# Blown_Fuse_LED.net
KiCad netlist of a schematic drawn in Altium Designer
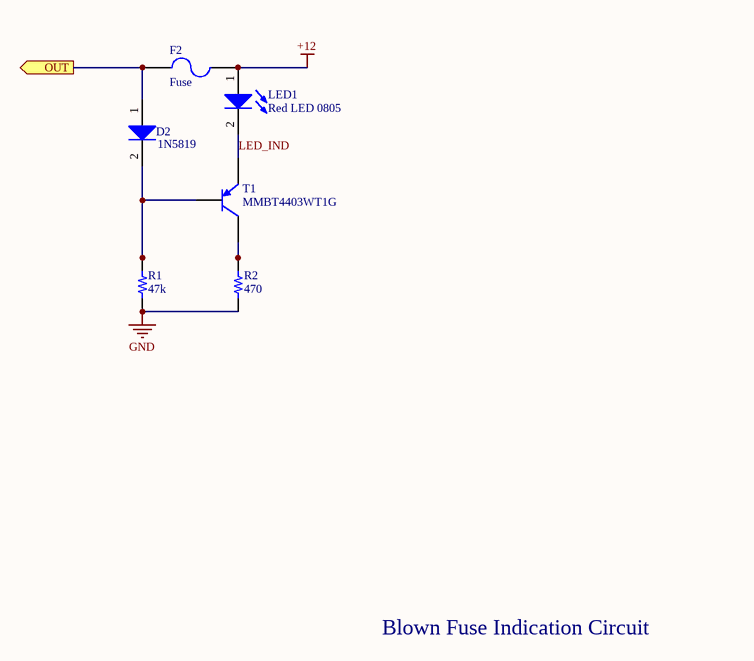
[diagram p0: Blown_Fuse_LED.SchDoc]

(export (version "E")
  (design (tool "Eeschema 10.0.6"))
  (components
    (comp (ref "D2")
      (value "1N5819")
      (footprint "SOD123F")
      (description "Diode Super Barrier 40V 1A Surface Mount SOD-123F")
      (fields (field (name "POWER") "40V") (field (name "MFRPARTNO") "1N5819HW1-7-F"))
      (libsource (lib "Altium-Lib") (part "DIODE"))
    )
    (comp (ref "F2")
      (value "Fuse")
      (footprint "3568-MiniFuseHolder")
      (libsource (lib "Altium-Lib") (part "Fuse"))
    )
    (comp (ref "LED1")
      (value "Red LED 0805")
      (footprint "0805_LED")
      (libsource (lib "Altium-Lib") (part "LED"))
    )
    (comp (ref "R1")
      (value "47k")
      (footprint "RES 0805/2012")
      (fields
        (field (name "TOLERANCE") "1%")
        (field (name "POWER") "1/10W")
        (field (name "Comment") "Resistor 47k 0805 1/10W 1%")
        (field (name "CREATED_BY") "Nick Mah")
      )
      (libsource (lib "Altium-Lib") (part "Resistor"))
    )
    (comp (ref "R2")
      (value "470")
      (footprint "RES 0805/2012")
      (fields
        (field (name "TOLERANCE") "1%")
        (field (name "POWER") "1/10W")
        (field (name "Comment") "Resistor 470 0805 1/10W 1%")
        (field (name "CREATED_BY") "Nick Mah")
      )
      (libsource (lib "Altium-Lib") (part "Resistor"))
    )
    (comp (ref "T1")
      (value "MMBT4403WT1G")
      (footprint "SOT23-3")
      (fields (field (name "CREATED_BY") "Angel"))
      (libsource (lib "Altium-Lib") (part "PNP Transistor"))
    )
  )
  (nets
    (net (code "1") (name "+12") (class "Default")
      (node (ref "F2") (pin "2") (pinfunction "2_2") (pintype "passive"))
      (node (ref "LED1") (pin "1") (pinfunction "A_1") (pintype "passive"))
    )
    (net (code "2") (name "/LED_IND") (class "Default")
      (node (ref "LED1") (pin "2") (pinfunction "K_2") (pintype "passive"))
      (node (ref "T1") (pin "2") (pinfunction "E_2") (pintype "passive"))
    )
    (net (code "3") (name "/OUT") (class "Default")
      (node (ref "D2") (pin "1") (pinfunction "A_1") (pintype "passive"))
      (node (ref "F2") (pin "1") (pinfunction "1_1") (pintype "passive"))
    )
    (net (code "4") (name "GND") (class "Default")
      (node (ref "R1") (pin "2") (pinfunction "2_2") (pintype "passive"))
      (node (ref "R2") (pin "2") (pinfunction "2_2") (pintype "passive"))
    )
    (net (code "5") (name "Net-(D2-K)") (class "Default")
      (node (ref "D2") (pin "2") (pinfunction "K_2") (pintype "passive"))
      (node (ref "R1") (pin "1") (pinfunction "1_1") (pintype "passive"))
      (node (ref "T1") (pin "1") (pinfunction "B_1") (pintype "passive"))
    )
    (net (code "6") (name "Net-(T1-C)") (class "Default")
      (node (ref "R2") (pin "1") (pinfunction "1_1") (pintype "passive"))
      (node (ref "T1") (pin "3") (pinfunction "C_3") (pintype "passive"))
    )
  )
)
